# Common_Bluetooth_Control.net
KiCad netlist of a schematic drawn in EAGLE
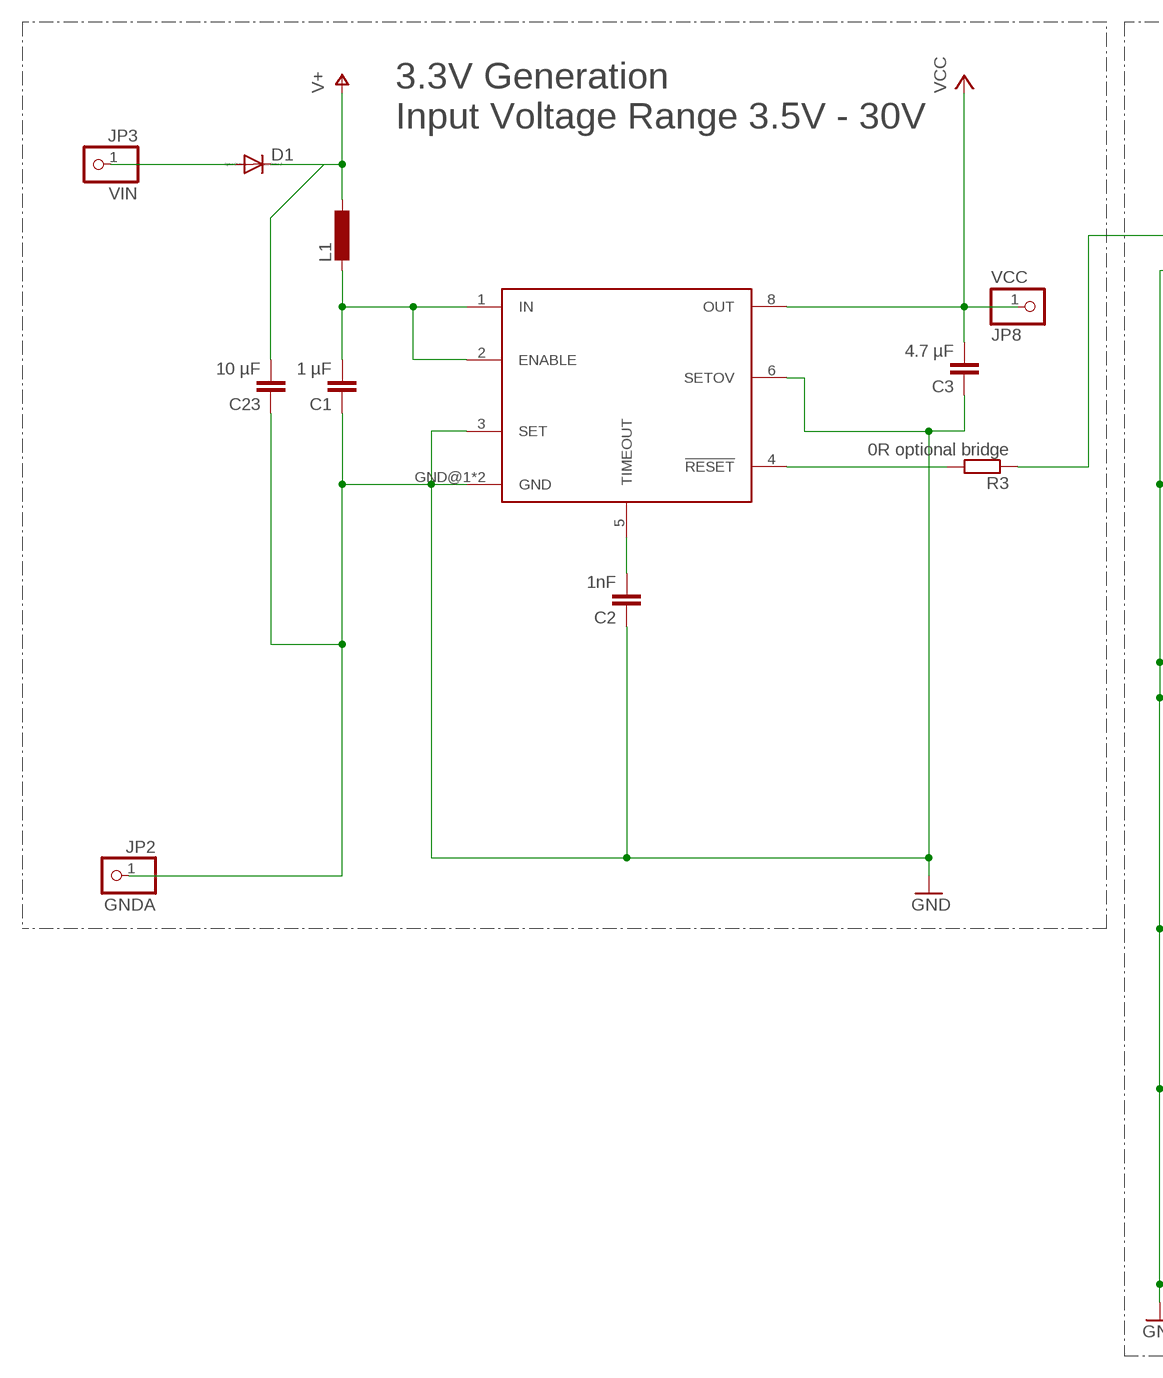
[diagram p0: schematic, sheet 1, part 1 of 2]
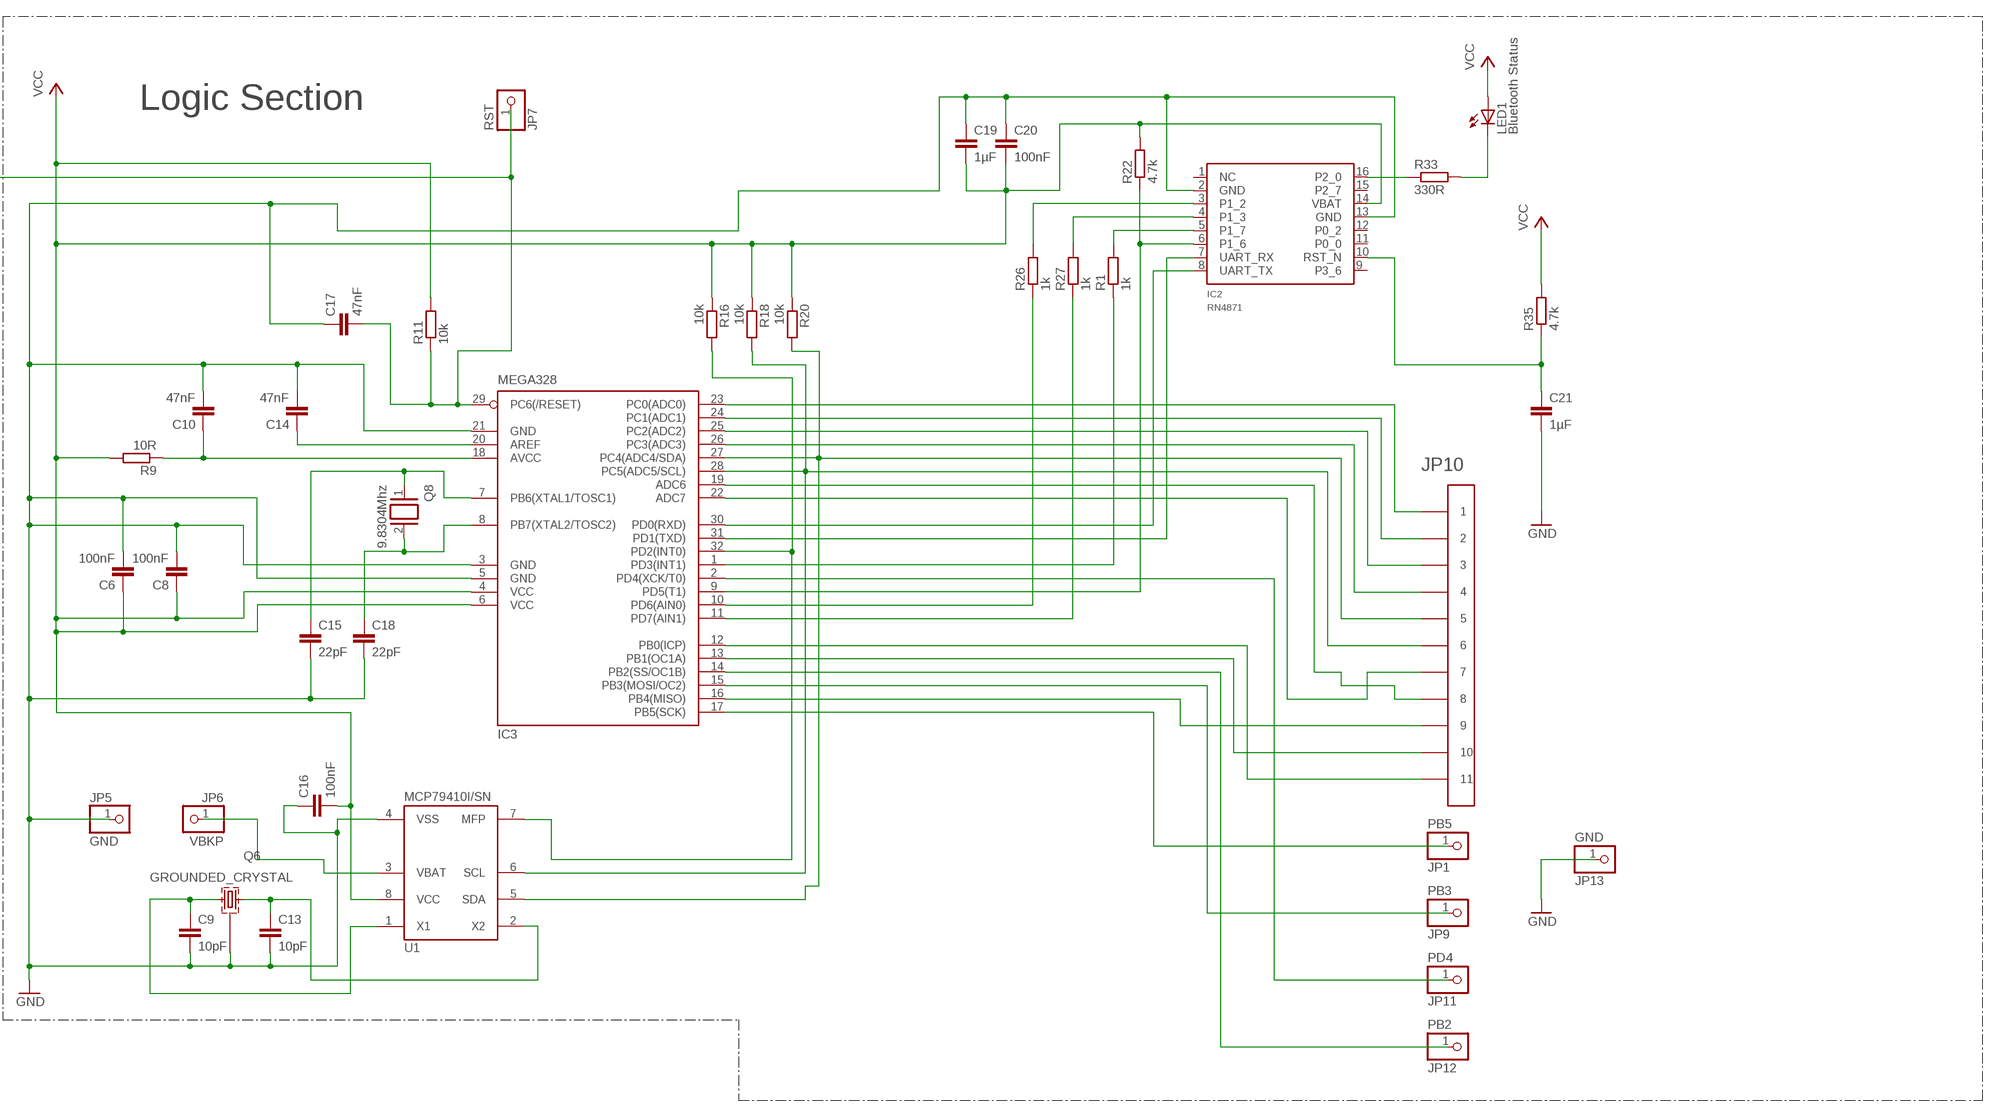
[diagram p1: schematic, sheet 1, part 2 of 2]

(export (version "E")
  (design (tool "Eeschema 10.0.6"))
  (components
    (comp (ref "C1")
      (value "1 µF")
      (footprint "eagle-import:C1206")
      (libsource (lib "eagle-import") (part "C-EUC1206"))
    )
    (comp (ref "C2")
      (value "1nF")
      (footprint "eagle-import:C0603")
      (libsource (lib "eagle-import") (part "C-EUC0603"))
    )
    (comp (ref "C3")
      (value "4.7 µF")
      (footprint "eagle-import:C1206")
      (libsource (lib "eagle-import") (part "C-EUC1206"))
    )
    (comp (ref "C6")
      (value "100nF")
      (footprint "eagle-import:C0603")
      (libsource (lib "eagle-import") (part "C-EUC0603"))
    )
    (comp (ref "C8")
      (value "100nF")
      (footprint "eagle-import:C0603K")
      (libsource (lib "eagle-import") (part "C-EUC0603K"))
    )
    (comp (ref "C9")
      (value "10pF")
      (footprint "eagle-import:C0603")
      (libsource (lib "eagle-import") (part "C-EUC0603"))
    )
    (comp (ref "C10")
      (value "47nF")
      (footprint "eagle-import:C0603")
      (libsource (lib "eagle-import") (part "C-EUC0603"))
    )
    (comp (ref "C13")
      (value "10pF")
      (footprint "eagle-import:C0603")
      (libsource (lib "eagle-import") (part "C-EUC0603"))
    )
    (comp (ref "C14")
      (value "47nF")
      (footprint "eagle-import:C0603")
      (libsource (lib "eagle-import") (part "C-EUC0603"))
    )
    (comp (ref "C15")
      (value "22pF")
      (footprint "eagle-import:C0805")
      (libsource (lib "eagle-import") (part "C-EUC0805"))
    )
    (comp (ref "C16")
      (value "100nF")
      (footprint "eagle-import:C0603")
      (libsource (lib "eagle-import") (part "C-EUC0603"))
    )
    (comp (ref "C17")
      (value "47nF")
      (footprint "eagle-import:C0603")
      (libsource (lib "eagle-import") (part "C-EUC0603"))
    )
    (comp (ref "C18")
      (value "22pF")
      (footprint "eagle-import:C0805")
      (libsource (lib "eagle-import") (part "C-EUC0805"))
    )
    (comp (ref "C19")
      (value "1µF")
      (footprint "eagle-import:C0603")
      (libsource (lib "eagle-import") (part "C-EUC0603"))
    )
    (comp (ref "C20")
      (value "100nF")
      (footprint "eagle-import:C0603")
      (libsource (lib "eagle-import") (part "C-EUC0603"))
    )
    (comp (ref "C21")
      (value "1µF")
      (footprint "eagle-import:C0603")
      (libsource (lib "eagle-import") (part "C-EUC0603"))
    )
    (comp (ref "C23")
      (value "10 µF")
      (footprint "eagle-import:C1206")
      (libsource (lib "eagle-import") (part "C-EUC1206"))
    )
    (comp (ref "D1")
      (value "DIODE-DO214AC")
      (footprint "eagle-import:DO214AC")
      (libsource (lib "eagle-import") (part "DIODE-DO214AC"))
    )
    (comp (ref "IC1")
      (value "MAX16910")
      (footprint "eagle-import:SO08")
      (libsource (lib "eagle-import") (part "MAX16910"))
    )
    (comp (ref "IC2")
      (value "RN4871")
      (footprint "eagle-import:RN4871")
      (libsource (lib "eagle-import") (part "RN4871"))
    )
    (comp (ref "IC3")
      (value "MEGA328")
      (footprint "eagle-import:TQFP32-08")
      (fields (field (name "MPN") "ATMEGA8-16AU"))
      (libsource (lib "eagle-import") (part "MEGA8-AI"))
    )
    (comp (ref "JP1")
      (value "PB5")
      (footprint "eagle-import:1X01")
      (libsource (lib "eagle-import") (part "PINHD-1X1"))
    )
    (comp (ref "JP2")
      (value "GNDA")
      (footprint "eagle-import:1X01")
      (libsource (lib "eagle-import") (part "PINHD-1X1"))
    )
    (comp (ref "JP3")
      (value "VIN")
      (footprint "eagle-import:1X01")
      (libsource (lib "eagle-import") (part "PINHD-1X1"))
    )
    (comp (ref "JP5")
      (value "GND")
      (footprint "eagle-import:1X01")
      (libsource (lib "eagle-import") (part "PINHD-1X1"))
    )
    (comp (ref "JP6")
      (value "VBKP")
      (footprint "eagle-import:1X01")
      (libsource (lib "eagle-import") (part "PINHD-1X1"))
    )
    (comp (ref "JP7")
      (value "RST")
      (footprint "eagle-import:1X01")
      (libsource (lib "eagle-import") (part "PINHD-1X1"))
    )
    (comp (ref "JP8")
      (value "VCC")
      (footprint "eagle-import:1X01")
      (libsource (lib "eagle-import") (part "PINHD-1X1"))
    )
    (comp (ref "JP9")
      (value "PB3")
      (footprint "eagle-import:1X01")
      (libsource (lib "eagle-import") (part "PINHD-1X1"))
    )
    (comp (ref "JP10")
      (value "PINHD-1X11-OCT")
      (footprint "eagle-import:1X11_OCT")
      (libsource (lib "eagle-import") (part "PINHD-1X11-OCT"))
    )
    (comp (ref "JP11")
      (value "PD4")
      (footprint "eagle-import:1X01")
      (libsource (lib "eagle-import") (part "PINHD-1X1"))
    )
    (comp (ref "JP12")
      (value "PB2")
      (footprint "eagle-import:1X01")
      (libsource (lib "eagle-import") (part "PINHD-1X1"))
    )
    (comp (ref "JP13")
      (value "GND")
      (footprint "eagle-import:1X01")
      (libsource (lib "eagle-import") (part "PINHD-1X1"))
    )
    (comp (ref "L1")
      (value "L-EUL0805")
      (footprint "eagle-import:R0805")
      (libsource (lib "eagle-import") (part "L-EUL0805"))
    )
    (comp (ref "LED1")
      (value "Bluetooth Status")
      (footprint "eagle-import:CHIPLED_0603")
      (libsource (lib "eagle-import") (part "LEDCHIPLED_0603"))
    )
    (comp (ref "Q6")
      (value "GROUNDED_CRYSTAL")
      (footprint "eagle-import:MS3V-7")
      (libsource (lib "eagle-import") (part "GROUNDED_CRYSTAL"))
    )
    (comp (ref "Q8")
      (value "9.8304Mhz")
      (footprint "eagle-import:QS")
      (libsource (lib "eagle-import") (part "XTAL/S"))
    )
    (comp (ref "R1")
      (value "1k")
      (footprint "eagle-import:R0603")
      (libsource (lib "eagle-import") (part "R-EU_R0603"))
    )
    (comp (ref "R3")
      (value "0R optional bridge")
      (footprint "eagle-import:R0603")
      (libsource (lib "eagle-import") (part "R-EU_R0603"))
    )
    (comp (ref "R9")
      (value "10R")
      (footprint "eagle-import:R0603")
      (libsource (lib "eagle-import") (part "R-EU_R0603"))
    )
    (comp (ref "R11")
      (value "10k")
      (footprint "eagle-import:R0603")
      (libsource (lib "eagle-import") (part "R-EU_R0603"))
    )
    (comp (ref "R16")
      (value "10k")
      (footprint "eagle-import:R0603")
      (libsource (lib "eagle-import") (part "R-EU_R0603"))
    )
    (comp (ref "R18")
      (value "10k")
      (footprint "eagle-import:R0603")
      (libsource (lib "eagle-import") (part "R-EU_R0603"))
    )
    (comp (ref "R20")
      (value "10k")
      (footprint "eagle-import:R0603")
      (libsource (lib "eagle-import") (part "R-EU_R0603"))
    )
    (comp (ref "R22")
      (value "4.7k")
      (footprint "eagle-import:R0603")
      (libsource (lib "eagle-import") (part "R-EU_R0603"))
    )
    (comp (ref "R26")
      (value "1k")
      (footprint "eagle-import:R0603")
      (libsource (lib "eagle-import") (part "R-EU_R0603"))
    )
    (comp (ref "R27")
      (value "1k")
      (footprint "eagle-import:R0603")
      (libsource (lib "eagle-import") (part "R-EU_R0603"))
    )
    (comp (ref "R33")
      (value "330R")
      (footprint "eagle-import:R0603")
      (libsource (lib "eagle-import") (part "R-EU_R0603"))
    )
    (comp (ref "R35")
      (value "4.7k")
      (footprint "eagle-import:R0603")
      (libsource (lib "eagle-import") (part "R-EU_R0603"))
    )
    (comp (ref "U1")
      (value "MCP79410I/SN")
      (footprint "eagle-import:SO8")
      (libsource (lib "eagle-import") (part "MCP7941?/SN0I"))
    )
  )
  (nets
    (net (code "1") (name "GND") (class "Default")
      (node (ref "C1") (pin "1") (pinfunction "1_1") (pintype "passive"))
      (node (ref "C10") (pin "2") (pinfunction "2_2") (pintype "passive"))
      (node (ref "C13") (pin "2") (pinfunction "2_2") (pintype "passive"))
      (node (ref "C14") (pin "2") (pinfunction "2_2") (pintype "passive"))
      (node (ref "C15") (pin "2") (pinfunction "2_2") (pintype "passive"))
      (node (ref "C16") (pin "1") (pinfunction "1_1") (pintype "passive"))
      (node (ref "C17") (pin "1") (pinfunction "1_1") (pintype "passive"))
      (node (ref "C18") (pin "2") (pinfunction "2_2") (pintype "passive"))
      (node (ref "C19") (pin "1") (pinfunction "1_1") (pintype "passive"))
      (node (ref "C2") (pin "1") (pinfunction "1_1") (pintype "passive"))
      (node (ref "C20") (pin "1") (pinfunction "1_1") (pintype "passive"))
      (node (ref "C21") (pin "2") (pinfunction "2_2") (pintype "passive"))
      (node (ref "C23") (pin "1") (pinfunction "1_1") (pintype "passive"))
      (node (ref "C3") (pin "1") (pinfunction "1_1") (pintype "passive"))
      (node (ref "C6") (pin "2") (pinfunction "2_2") (pintype "passive"))
      (node (ref "C8") (pin "2") (pinfunction "2_2") (pintype "passive"))
      (node (ref "C9") (pin "2") (pinfunction "2_2") (pintype "passive"))
      (node (ref "IC1") (pin "3") (pinfunction "SET_3") (pintype "bidirectional"))
      (node (ref "IC1") (pin "6") (pinfunction "SETOV_6") (pintype "bidirectional"))
      (node (ref "IC1") (pin "GND@1") (pinfunction "GND_GND@1") (pintype "bidirectional"))
      (node (ref "IC1") (pin "GND@2") (pinfunction "GND_GND@2") (pintype "bidirectional"))
      (node (ref "IC2") (pin "13") (pinfunction "GND_13") (pintype "bidirectional"))
      (node (ref "IC2") (pin "2") (pinfunction "GND_2") (pintype "bidirectional"))
      (node (ref "IC3") (pin "21") (pinfunction "GND_21") (pintype "power_in"))
      (node (ref "IC3") (pin "3") (pinfunction "GND_3") (pintype "power_in"))
      (node (ref "IC3") (pin "5") (pinfunction "GND_5") (pintype "power_in"))
      (node (ref "JP13") (pin "1") (pinfunction "1_1") (pintype "passive"))
      (node (ref "JP2") (pin "1") (pinfunction "1_1") (pintype "passive"))
      (node (ref "JP5") (pin "1") (pinfunction "1_1") (pintype "passive"))
      (node (ref "Q6") (pin "GND") (pinfunction "GND_GND") (pintype "bidirectional"))
      (node (ref "U1") (pin "4") (pinfunction "VSS_4") (pintype "power_in"))
    )
    (net (code "2") (name "Net-(D1-PadA)") (class "Default")
      (node (ref "D1") (pin "A") (pinfunction "A_A") (pintype "passive"))
      (node (ref "JP3") (pin "1") (pinfunction "1_1") (pintype "passive"))
    )
    (net (code "3") (name "Net-(IC1-ENABLE)") (class "Default")
      (node (ref "C1") (pin "2") (pinfunction "2_2") (pintype "passive"))
      (node (ref "IC1") (pin "1") (pinfunction "IN_1") (pintype "input"))
      (node (ref "IC1") (pin "2") (pinfunction "ENABLE_2") (pintype "input"))
      (node (ref "L1") (pin "2") (pinfunction "2_2") (pintype "passive"))
    )
    (net (code "4") (name "Net-(IC1-TIMEOUT)") (class "Default")
      (node (ref "C2") (pin "2") (pinfunction "2_2") (pintype "passive"))
      (node (ref "IC1") (pin "5") (pinfunction "TIMEOUT_5") (pintype "bidirectional"))
    )
    (net (code "5") (name "Net-(IC1-~{RESET})") (class "Default")
      (node (ref "IC1") (pin "4") (pinfunction "~{RESET}_4") (pintype "bidirectional"))
      (node (ref "R3") (pin "2") (pinfunction "2_2") (pintype "passive"))
    )
    (net (code "6") (name "Net-(IC2-P1_2)") (class "Default")
      (node (ref "IC2") (pin "3") (pinfunction "P1_2_3") (pintype "bidirectional"))
      (node (ref "R26") (pin "2") (pinfunction "2_2") (pintype "passive"))
    )
    (net (code "7") (name "Net-(IC2-P1_3)") (class "Default")
      (node (ref "IC2") (pin "4") (pinfunction "P1_3_4") (pintype "bidirectional"))
      (node (ref "R27") (pin "2") (pinfunction "2_2") (pintype "passive"))
    )
    (net (code "8") (name "Net-(IC2-P1_6)") (class "Default")
      (node (ref "IC2") (pin "6") (pinfunction "P1_6_6") (pintype "bidirectional"))
      (node (ref "IC3") (pin "9") (pinfunction "PD5(T1)_9") (pintype "bidirectional"))
      (node (ref "R22") (pin "1") (pinfunction "1_1") (pintype "passive"))
    )
    (net (code "9") (name "Net-(IC2-P1_7)") (class "Default")
      (node (ref "IC2") (pin "5") (pinfunction "P1_7_5") (pintype "bidirectional"))
      (node (ref "R1") (pin "2") (pinfunction "2_2") (pintype "passive"))
    )
    (net (code "10") (name "Net-(IC2-P2_0)") (class "Default")
      (node (ref "IC2") (pin "16") (pinfunction "P2_0_16") (pintype "bidirectional"))
      (node (ref "R33") (pin "1") (pinfunction "1_1") (pintype "passive"))
    )
    (net (code "11") (name "Net-(IC2-RST_N)") (class "Default")
      (node (ref "C21") (pin "1") (pinfunction "1_1") (pintype "passive"))
      (node (ref "IC2") (pin "10") (pinfunction "RST_N_10") (pintype "bidirectional"))
      (node (ref "R35") (pin "1") (pinfunction "1_1") (pintype "passive"))
    )
    (net (code "12") (name "Net-(IC2-UART_RX)") (class "Default")
      (node (ref "IC2") (pin "7") (pinfunction "UART_RX_7") (pintype "bidirectional"))
      (node (ref "IC3") (pin "31") (pinfunction "PD1(TXD)_31") (pintype "bidirectional"))
    )
    (net (code "13") (name "Net-(IC2-UART_TX)") (class "Default")
      (node (ref "IC2") (pin "8") (pinfunction "UART_TX_8") (pintype "bidirectional"))
      (node (ref "IC3") (pin "30") (pinfunction "PD0(RXD)_30") (pintype "bidirectional"))
    )
    (net (code "14") (name "Net-(IC3-ADC6)") (class "Default")
      (node (ref "IC3") (pin "19") (pinfunction "ADC6_19") (pintype "bidirectional"))
      (node (ref "JP10") (pin "8") (pinfunction "8_8") (pintype "bidirectional"))
    )
    (net (code "15") (name "Net-(IC3-ADC7)") (class "Default")
      (node (ref "IC3") (pin "22") (pinfunction "ADC7_22") (pintype "bidirectional"))
      (node (ref "JP10") (pin "7") (pinfunction "7_7") (pintype "bidirectional"))
    )
    (net (code "16") (name "Net-(IC3-AREF)") (class "Default")
      (node (ref "C14") (pin "1") (pinfunction "1_1") (pintype "passive"))
      (node (ref "IC3") (pin "20") (pinfunction "AREF_20") (pintype "passive"))
    )
    (net (code "17") (name "Net-(IC3-AVCC)") (class "Default")
      (node (ref "C10") (pin "1") (pinfunction "1_1") (pintype "passive"))
      (node (ref "IC3") (pin "18") (pinfunction "AVCC_18") (pintype "power_in"))
      (node (ref "R9") (pin "1") (pinfunction "1_1") (pintype "passive"))
    )
    (net (code "18") (name "Net-(IC3-PB0(ICP))") (class "Default")
      (node (ref "IC3") (pin "12") (pinfunction "PB0(ICP)_12") (pintype "bidirectional"))
      (node (ref "JP10") (pin "11") (pinfunction "11_11") (pintype "bidirectional"))
    )
    (net (code "19") (name "Net-(IC3-PB1(OC1A))") (class "Default")
      (node (ref "IC3") (pin "13") (pinfunction "PB1(OC1A)_13") (pintype "bidirectional"))
      (node (ref "JP10") (pin "10") (pinfunction "10_10") (pintype "bidirectional"))
    )
    (net (code "20") (name "Net-(IC3-PB2(SS{slash}OC1B))") (class "Default")
      (node (ref "IC3") (pin "14") (pinfunction "PB2(SS/OC1B)_14") (pintype "bidirectional"))
      (node (ref "JP12") (pin "1") (pinfunction "1_1") (pintype "passive"))
    )
    (net (code "21") (name "Net-(IC3-PB3(MOSI{slash}OC2))") (class "Default")
      (node (ref "IC3") (pin "15") (pinfunction "PB3(MOSI/OC2)_15") (pintype "bidirectional"))
      (node (ref "JP9") (pin "1") (pinfunction "1_1") (pintype "passive"))
    )
    (net (code "22") (name "Net-(IC3-PB4(MISO))") (class "Default")
      (node (ref "IC3") (pin "16") (pinfunction "PB4(MISO)_16") (pintype "bidirectional"))
      (node (ref "JP10") (pin "9") (pinfunction "9_9") (pintype "bidirectional"))
    )
    (net (code "23") (name "Net-(IC3-PB5(SCK))") (class "Default")
      (node (ref "IC3") (pin "17") (pinfunction "PB5(SCK)_17") (pintype "bidirectional"))
      (node (ref "JP1") (pin "1") (pinfunction "1_1") (pintype "passive"))
    )
    (net (code "24") (name "Net-(IC3-PB6(XTAL1{slash}TOSC1))") (class "Default")
      (node (ref "C15") (pin "1") (pinfunction "1_1") (pintype "passive"))
      (node (ref "IC3") (pin "7") (pinfunction "PB6(XTAL1/TOSC1)_7") (pintype "bidirectional"))
      (node (ref "Q8") (pin "1") (pinfunction "1_1") (pintype "passive"))
    )
    (net (code "25") (name "Net-(IC3-PB7(XTAL2{slash}TOSC2))") (class "Default")
      (node (ref "C18") (pin "1") (pinfunction "1_1") (pintype "passive"))
      (node (ref "IC3") (pin "8") (pinfunction "PB7(XTAL2/TOSC2)_8") (pintype "bidirectional"))
      (node (ref "Q8") (pin "2") (pinfunction "2_2") (pintype "passive"))
    )
    (net (code "26") (name "Net-(IC3-PC0(ADC0))") (class "Default")
      (node (ref "IC3") (pin "23") (pinfunction "PC0(ADC0)_23") (pintype "bidirectional"))
      (node (ref "JP10") (pin "5") (pinfunction "1_5") (pintype "bidirectional"))
    )
    (net (code "27") (name "Net-(IC3-PC1(ADC1))") (class "Default")
      (node (ref "IC3") (pin "24") (pinfunction "PC1(ADC1)_24") (pintype "bidirectional"))
      (node (ref "JP10") (pin "6") (pinfunction "2_6") (pintype "bidirectional"))
    )
    (net (code "28") (name "Net-(IC3-PC2(ADC2))") (class "Default")
      (node (ref "IC3") (pin "25") (pinfunction "PC2(ADC2)_25") (pintype "bidirectional"))
      (node (ref "JP10") (pin "4") (pinfunction "3_4") (pintype "bidirectional"))
    )
    (net (code "29") (name "Net-(IC3-PC3(ADC3))") (class "Default")
      (node (ref "IC3") (pin "26") (pinfunction "PC3(ADC3)_26") (pintype "bidirectional"))
      (node (ref "JP10") (pin "3") (pinfunction "4_3") (pintype "bidirectional"))
    )
    (net (code "30") (name "Net-(IC3-PC4(ADC4{slash}SDA))") (class "Default")
      (node (ref "IC3") (pin "27") (pinfunction "PC4(ADC4/SDA)_27") (pintype "bidirectional"))
      (node (ref "JP10") (pin "2") (pinfunction "5_2") (pintype "bidirectional"))
      (node (ref "R20") (pin "2") (pinfunction "2_2") (pintype "passive"))
      (node (ref "U1") (pin "5") (pinfunction "SDA_5") (pintype "open_collector"))
    )
    (net (code "31") (name "Net-(IC3-PC5(ADC5{slash}SCL))") (class "Default")
      (node (ref "IC3") (pin "28") (pinfunction "PC5(ADC5/SCL)_28") (pintype "bidirectional"))
      (node (ref "JP10") (pin "1") (pinfunction "6_1") (pintype "bidirectional"))
      (node (ref "R18") (pin "2") (pinfunction "2_2") (pintype "passive"))
      (node (ref "U1") (pin "6") (pinfunction "SCL_6") (pintype "input"))
    )
    (net (code "32") (name "Net-(IC3-PC6({slash}RESET))") (class "Default")
      (node (ref "C17") (pin "2") (pinfunction "2_2") (pintype "passive"))
      (node (ref "IC3") (pin "29") (pinfunction "PC6(/RESET)_29") (pintype "bidirectional"))
      (node (ref "JP7") (pin "1") (pinfunction "1_1") (pintype "passive"))
      (node (ref "R11") (pin "1") (pinfunction "1_1") (pintype "passive"))
      (node (ref "R3") (pin "1") (pinfunction "1_1") (pintype "passive"))
    )
    (net (code "33") (name "Net-(IC3-PD2(INT0))") (class "Default")
      (node (ref "IC3") (pin "32") (pinfunction "PD2(INT0)_32") (pintype "bidirectional"))
      (node (ref "R16") (pin "2") (pinfunction "2_2") (pintype "passive"))
      (node (ref "U1") (pin "7") (pinfunction "MFP_7") (pintype "open_collector"))
    )
    (net (code "34") (name "Net-(IC3-PD3(INT1))") (class "Default")
      (node (ref "IC3") (pin "1") (pinfunction "PD3(INT1)_1") (pintype "bidirectional"))
      (node (ref "R1") (pin "1") (pinfunction "1_1") (pintype "passive"))
    )
    (net (code "35") (name "Net-(IC3-PD4(XCK{slash}T0))") (class "Default")
      (node (ref "IC3") (pin "2") (pinfunction "PD4(XCK/T0)_2") (pintype "bidirectional"))
      (node (ref "JP11") (pin "1") (pinfunction "1_1") (pintype "passive"))
    )
    (net (code "36") (name "Net-(IC3-PD6(AIN0))") (class "Default")
      (node (ref "IC3") (pin "10") (pinfunction "PD6(AIN0)_10") (pintype "bidirectional"))
      (node (ref "R26") (pin "1") (pinfunction "1_1") (pintype "passive"))
    )
    (net (code "37") (name "Net-(IC3-PD7(AIN1))") (class "Default")
      (node (ref "IC3") (pin "11") (pinfunction "PD7(AIN1)_11") (pintype "bidirectional"))
      (node (ref "R27") (pin "1") (pinfunction "1_1") (pintype "passive"))
    )
    (net (code "38") (name "Net-(LED1-PadC)") (class "Default")
      (node (ref "LED1") (pin "C") (pinfunction "C_C") (pintype "passive"))
      (node (ref "R33") (pin "2") (pinfunction "2_2") (pintype "passive"))
    )
    (net (code "39") (name "Net-(Q6-1)") (class "Default")
      (node (ref "C9") (pin "1") (pinfunction "1_1") (pintype "passive"))
      (node (ref "Q6") (pin "X1") (pinfunction "1_X1") (pintype "passive"))
      (node (ref "U1") (pin "1") (pinfunction "X1_1") (pintype "input"))
    )
    (net (code "40") (name "Net-(Q6-2)") (class "Default")
      (node (ref "C13") (pin "1") (pinfunction "1_1") (pintype "passive"))
      (node (ref "Q6") (pin "X2") (pinfunction "2_X2") (pintype "passive"))
      (node (ref "U1") (pin "2") (pinfunction "X2_2") (pintype "output"))
    )
    (net (code "41") (name "Net-(U1-VBAT)") (class "Default")
      (node (ref "JP6") (pin "1") (pinfunction "1_1") (pintype "passive"))
      (node (ref "U1") (pin "3") (pinfunction "VBAT_3") (pintype "power_in"))
    )
    (net (code "42") (name "V+") (class "Default")
      (node (ref "C23") (pin "2") (pinfunction "2_2") (pintype "passive"))
      (node (ref "D1") (pin "C") (pinfunction "C_C") (pintype "passive"))
      (node (ref "L1") (pin "1") (pinfunction "1_1") (pintype "passive"))
    )
    (net (code "43") (name "VCC") (class "Default")
      (node (ref "C16") (pin "2") (pinfunction "2_2") (pintype "passive"))
      (node (ref "C19") (pin "2") (pinfunction "2_2") (pintype "passive"))
      (node (ref "C20") (pin "2") (pinfunction "2_2") (pintype "passive"))
      (node (ref "C3") (pin "2") (pinfunction "2_2") (pintype "passive"))
      (node (ref "C6") (pin "1") (pinfunction "1_1") (pintype "passive"))
      (node (ref "C8") (pin "1") (pinfunction "1_1") (pintype "passive"))
      (node (ref "IC1") (pin "8") (pinfunction "OUT_8") (pintype "output"))
      (node (ref "IC2") (pin "14") (pinfunction "VBAT_14") (pintype "bidirectional"))
      (node (ref "IC3") (pin "4") (pinfunction "VCC_4") (pintype "power_in"))
      (node (ref "IC3") (pin "6") (pinfunction "VCC_6") (pintype "power_in"))
      (node (ref "JP8") (pin "1") (pinfunction "1_1") (pintype "passive"))
      (node (ref "LED1") (pin "A") (pinfunction "A_A") (pintype "passive"))
      (node (ref "R11") (pin "2") (pinfunction "2_2") (pintype "passive"))
      (node (ref "R16") (pin "1") (pinfunction "1_1") (pintype "passive"))
      (node (ref "R18") (pin "1") (pinfunction "1_1") (pintype "passive"))
      (node (ref "R20") (pin "1") (pinfunction "1_1") (pintype "passive"))
      (node (ref "R22") (pin "2") (pinfunction "2_2") (pintype "passive"))
      (node (ref "R35") (pin "2") (pinfunction "2_2") (pintype "passive"))
      (node (ref "R9") (pin "2") (pinfunction "2_2") (pintype "passive"))
      (node (ref "U1") (pin "8") (pinfunction "VCC_8") (pintype "power_in"))
    )
    (net (code "44") (name "unconnected-(IC2-NC-Pad1)") (class "Default")
      (node (ref "IC2") (pin "1") (pinfunction "NC_1") (pintype "bidirectional"))
    )
    (net (code "45") (name "unconnected-(IC2-P0_0-Pad11)") (class "Default")
      (node (ref "IC2") (pin "11") (pinfunction "P0_0_11") (pintype "bidirectional"))
    )
    (net (code "46") (name "unconnected-(IC2-P0_2-Pad12)") (class "Default")
      (node (ref "IC2") (pin "12") (pinfunction "P0_2_12") (pintype "bidirectional"))
    )
    (net (code "47") (name "unconnected-(IC2-P2_7-Pad15)") (class "Default")
      (node (ref "IC2") (pin "15") (pinfunction "P2_7_15") (pintype "bidirectional"))
    )
    (net (code "48") (name "unconnected-(IC2-P3_6-Pad9)") (class "Default")
      (node (ref "IC2") (pin "9") (pinfunction "P3_6_9") (pintype "bidirectional"))
    )
  )
)
